# mdv_commutator_v2.net
KiCad netlist of a schematic drawn in Altium Designer
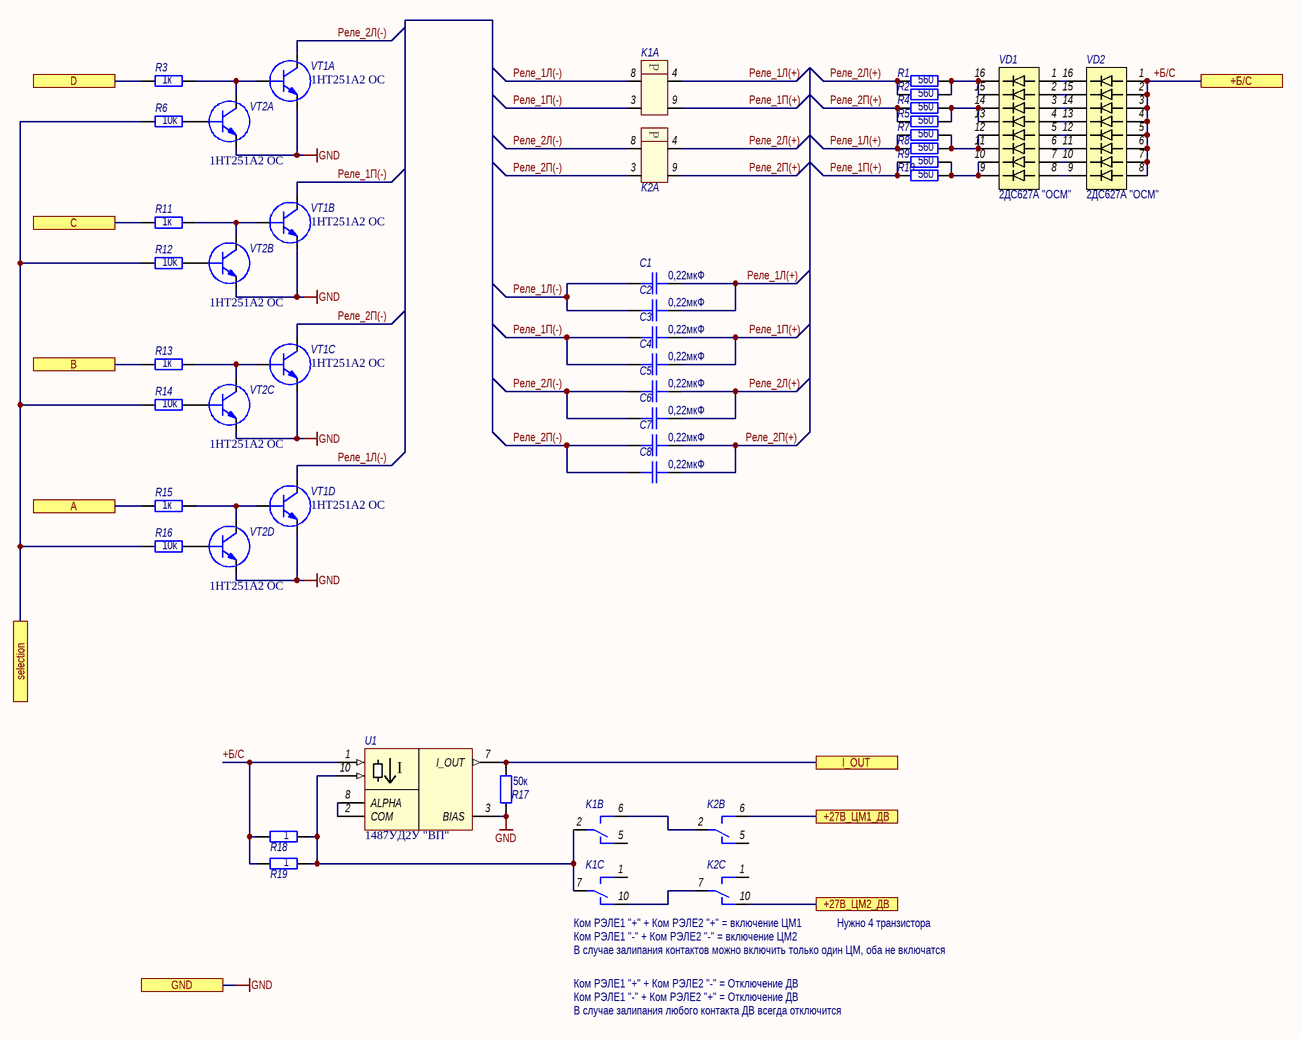
[diagram p0: mdv_commutator_v2.SchDoc]

(export (version "E")
  (design (tool "Eeschema 10.0.6"))
  (components
    (comp (ref "C1")
      (value "0,22мкФ")
      (footprint "SMD_C0402")
      (description "Capacitor")
      (fields (field (name "Comment") "K10-79"))
      (libsource (lib "Passive") (part "Capacitor"))
    )
    (comp (ref "C2")
      (value "0,22мкФ")
      (footprint "SMD_C0402")
      (description "Capacitor")
      (fields (field (name "Comment") "K10-79"))
      (libsource (lib "Passive") (part "Capacitor"))
    )
    (comp (ref "C3")
      (value "0,22мкФ")
      (footprint "SMD_C0402")
      (description "Capacitor")
      (fields (field (name "Comment") "K10-79"))
      (libsource (lib "Passive") (part "Capacitor"))
    )
    (comp (ref "C4")
      (value "0,22мкФ")
      (footprint "SMD_C0402")
      (description "Capacitor")
      (fields (field (name "Comment") "K10-79"))
      (libsource (lib "Passive") (part "Capacitor"))
    )
    (comp (ref "C5")
      (value "0,22мкФ")
      (footprint "SMD_C0402")
      (description "Capacitor")
      (fields (field (name "Comment") "K10-79"))
      (libsource (lib "Passive") (part "Capacitor"))
    )
    (comp (ref "C6")
      (value "0,22мкФ")
      (footprint "SMD_C0402")
      (description "Capacitor")
      (fields (field (name "Comment") "K10-79"))
      (libsource (lib "Passive") (part "Capacitor"))
    )
    (comp (ref "C7")
      (value "0,22мкФ")
      (footprint "SMD_C0402")
      (description "Capacitor")
      (fields (field (name "Comment") "K10-79"))
      (libsource (lib "Passive") (part "Capacitor"))
    )
    (comp (ref "C8")
      (value "0,22мкФ")
      (footprint "SMD_C0402")
      (description "Capacitor")
      (fields (field (name "Comment") "K10-79"))
      (libsource (lib "Passive") (part "Capacitor"))
    )
    (comp (ref "K1")
      (value "RPS45-1-T-OS")
      (footprint "RPS-45-1")
      (description "Реле поляризованное")
      (libsource (lib "Commutator") (part "RPS45"))
    )
    (comp (ref "K2")
      (value "RPS45-1-T-OS")
      (footprint "RPS-45-1")
      (description "Реле поляризованное")
      (libsource (lib "Commutator") (part "RPS45"))
    )
    (comp (ref "R1")
      (value "560")
      (footprint "SMD_0805")
      (description "Resistor")
      (fields (field (name "Comment") "OSM R1-12"))
      (libsource (lib "Passive") (part "Resistor"))
    )
    (comp (ref "R2")
      (value "560")
      (footprint "SMD_0805")
      (description "Resistor")
      (fields (field (name "Comment") "OSM R1-12"))
      (libsource (lib "Passive") (part "Resistor"))
    )
    (comp (ref "R3")
      (value "1к")
      (footprint "SMD_0805")
      (description "Resistor")
      (fields (field (name "Comment") "OSM R1-12"))
      (libsource (lib "Passive") (part "Resistor"))
    )
    (comp (ref "R4")
      (value "560")
      (footprint "SMD_0805")
      (description "Resistor")
      (fields (field (name "Comment") "OSM R1-12"))
      (libsource (lib "Passive") (part "Resistor"))
    )
    (comp (ref "R5")
      (value "560")
      (footprint "SMD_0805")
      (description "Resistor")
      (fields (field (name "Comment") "OSM R1-12"))
      (libsource (lib "Passive") (part "Resistor"))
    )
    (comp (ref "R6")
      (value "10k")
      (footprint "SMD_0805")
      (description "Resistor")
      (fields (field (name "Comment") "OSM R1-12"))
      (libsource (lib "Passive") (part "Resistor"))
    )
    (comp (ref "R7")
      (value "560")
      (footprint "SMD_0805")
      (description "Resistor")
      (fields (field (name "Comment") "OSM R1-12"))
      (libsource (lib "Passive") (part "Resistor"))
    )
    (comp (ref "R8")
      (value "560")
      (footprint "SMD_0805")
      (description "Resistor")
      (fields (field (name "Comment") "OSM R1-12"))
      (libsource (lib "Passive") (part "Resistor"))
    )
    (comp (ref "R9")
      (value "560")
      (footprint "SMD_0805")
      (description "Resistor")
      (fields (field (name "Comment") "OSM R1-12"))
      (libsource (lib "Passive") (part "Resistor"))
    )
    (comp (ref "R10")
      (value "560")
      (footprint "SMD_0805")
      (description "Resistor")
      (fields (field (name "Comment") "OSM R1-12"))
      (libsource (lib "Passive") (part "Resistor"))
    )
    (comp (ref "R11")
      (value "1к")
      (footprint "SMD_0805")
      (description "Resistor")
      (fields (field (name "Comment") "OSM R1-12"))
      (libsource (lib "Passive") (part "Resistor"))
    )
    (comp (ref "R12")
      (value "10k")
      (footprint "SMD_0805")
      (description "Resistor")
      (fields (field (name "Comment") "OSM R1-12"))
      (libsource (lib "Passive") (part "Resistor"))
    )
    (comp (ref "R13")
      (value "1к")
      (footprint "SMD_0805")
      (description "Resistor")
      (fields (field (name "Comment") "OSM R1-12"))
      (libsource (lib "Passive") (part "Resistor"))
    )
    (comp (ref "R14")
      (value "10k")
      (footprint "SMD_0805")
      (description "Resistor")
      (fields (field (name "Comment") "OSM R1-12"))
      (libsource (lib "Passive") (part "Resistor"))
    )
    (comp (ref "R15")
      (value "1к")
      (footprint "SMD_0805")
      (description "Resistor")
      (fields (field (name "Comment") "OSM R1-12"))
      (libsource (lib "Passive") (part "Resistor"))
    )
    (comp (ref "R16")
      (value "10k")
      (footprint "SMD_0805")
      (description "Resistor")
      (fields (field (name "Comment") "OSM R1-12"))
      (libsource (lib "Passive") (part "Resistor"))
    )
    (comp (ref "R17")
      (value "50к")
      (footprint "SMD_0805")
      (description "Resistor")
      (fields (field (name "Comment") "OSM R1-12"))
      (libsource (lib "") (part "Resistor_2"))
    )
    (comp (ref "R18")
      (value "1")
      (footprint "SMD_0805")
      (description "Resistor")
      (fields (field (name "Comment") "OSM R1-12"))
      (libsource (lib "") (part "Resistor_1"))
    )
    (comp (ref "R19")
      (value "1")
      (footprint "SMD_0805")
      (description "Resistor")
      (fields (field (name "Comment") "OSM R1-12"))
      (libsource (lib "") (part "Resistor_1"))
    )
    (comp (ref "U1")
      (value "1487UD2U")
      (footprint "FlatPack-10")
      (fields (field (name "НАИМЕНОВАНИЕ") "1487УД2У \"ВП\""))
      (libsource (lib "Power_Monitor") (part "AD8212S"))
    )
    (comp (ref "VD1")
      (value "2DS627A OSM")
      (footprint "401.16-3")
      (description "Диодная матрица")
      (fields (field (name "НАИМЕНОВАНИЕ") "2ДС627А \"ОСМ\""))
      (libsource (lib "Diod") (part "2DS627A"))
    )
    (comp (ref "VD2")
      (value "2DS627A OSM")
      (footprint "401.16-3")
      (description "Диодная матрица")
      (fields (field (name "НАИМЕНОВАНИЕ") "2ДС627А \"ОСМ\""))
      (libsource (lib "Diod") (part "2DS627A"))
    )
    (comp (ref "VT1")
      (value "1NT251A2 OS")
      (footprint "FlatPack-14.PcbLib")
      (description "Транзисторная сборка")
      (fields (field (name "НАИМЕНОВАНИЕ") "1НТ251А2 ОС"))
      (libsource (lib "1NT251A2 OS") (part "1NT251A2 OS"))
    )
    (comp (ref "VT2")
      (value "1NT251A2 OS")
      (footprint "FlatPack-14.PcbLib")
      (description "Транзисторная сборка")
      (fields (field (name "НАИМЕНОВАНИЕ") "1НТ251А2 ОС"))
      (libsource (lib "1NT251A2 OS") (part "1NT251A2 OS"))
    )
  )
  (nets
    (net (code "1") (name "/+27В_ЦМ1_ДВ") (class "Default")
      (node (ref "K2") (pin "6") (pinfunction "6_6") (pintype "passive"))
    )
    (net (code "2") (name "/+27В_ЦМ2_ДВ") (class "Default")
      (node (ref "K2") (pin "10") (pinfunction "10_10") (pintype "passive"))
    )
    (net (code "3") (name "/+Б{slash}С") (class "Default")
      (node (ref "R18") (pin "2") (pinfunction "2_2") (pintype "passive"))
      (node (ref "R19") (pin "2") (pinfunction "2_2") (pintype "passive"))
      (node (ref "U1") (pin "1") (pinfunction "V+_1") (pintype "input"))
      (node (ref "VD2") (pin "1") (pinfunction "1A_1") (pintype "passive"))
      (node (ref "VD2") (pin "2") (pinfunction "1B_2") (pintype "passive"))
      (node (ref "VD2") (pin "3") (pinfunction "1C_3") (pintype "passive"))
      (node (ref "VD2") (pin "4") (pinfunction "1D_4") (pintype "passive"))
      (node (ref "VD2") (pin "5") (pinfunction "1E_5") (pintype "passive"))
      (node (ref "VD2") (pin "6") (pinfunction "1F_6") (pintype "passive"))
      (node (ref "VD2") (pin "7") (pinfunction "1G_7") (pintype "passive"))
      (node (ref "VD2") (pin "8") (pinfunction "1H_8") (pintype "passive"))
    )
    (net (code "4") (name "/A") (class "Default")
      (node (ref "R15") (pin "1") (pinfunction "1_1") (pintype "passive"))
    )
    (net (code "5") (name "/B") (class "Default")
      (node (ref "R13") (pin "1") (pinfunction "1_1") (pintype "passive"))
    )
    (net (code "6") (name "/C") (class "Default")
      (node (ref "R11") (pin "1") (pinfunction "1_1") (pintype "passive"))
    )
    (net (code "7") (name "/D") (class "Default")
      (node (ref "R3") (pin "1") (pinfunction "1_1") (pintype "passive"))
    )
    (net (code "8") (name "/I_OUT") (class "Default")
      (node (ref "R17") (pin "2") (pinfunction "2_2") (pintype "passive"))
      (node (ref "U1") (pin "7") (pinfunction "I_OUT_7") (pintype "output"))
    )
    (net (code "9") (name "/selection") (class "Default")
      (node (ref "R12") (pin "1") (pinfunction "1_1") (pintype "passive"))
      (node (ref "R14") (pin "1") (pinfunction "1_1") (pintype "passive"))
      (node (ref "R16") (pin "1") (pinfunction "1_1") (pintype "passive"))
      (node (ref "R6") (pin "1") (pinfunction "1_1") (pintype "passive"))
    )
    (net (code "10") (name "/Реле_1Л(+)") (class "Default")
      (node (ref "C1") (pin "2") (pinfunction "2_2") (pintype "passive"))
      (node (ref "C2") (pin "2") (pinfunction "2_2") (pintype "passive"))
      (node (ref "K1") (pin "4") (pinfunction "4_4") (pintype "passive"))
      (node (ref "R7") (pin "1") (pinfunction "1_1") (pintype "passive"))
      (node (ref "R8") (pin "1") (pinfunction "1_1") (pintype "passive"))
    )
    (net (code "11") (name "/Реле_1Л(-)") (class "Default")
      (node (ref "C1") (pin "1") (pinfunction "1_1") (pintype "passive"))
      (node (ref "C2") (pin "1") (pinfunction "1_1") (pintype "passive"))
      (node (ref "K1") (pin "8") (pinfunction "8_8") (pintype "passive"))
      (node (ref "VT1") (pin "7") (pinfunction "C_7") (pintype "passive"))
    )
    (net (code "12") (name "/Реле_1П(+)") (class "Default")
      (node (ref "C3") (pin "2") (pinfunction "2_2") (pintype "passive"))
      (node (ref "C4") (pin "2") (pinfunction "2_2") (pintype "passive"))
      (node (ref "K1") (pin "9") (pinfunction "9_9") (pintype "passive"))
      (node (ref "R10") (pin "1") (pinfunction "1_1") (pintype "passive"))
      (node (ref "R9") (pin "1") (pinfunction "1_1") (pintype "passive"))
    )
    (net (code "13") (name "/Реле_1П(-)") (class "Default")
      (node (ref "C3") (pin "1") (pinfunction "1_1") (pintype "passive"))
      (node (ref "C4") (pin "1") (pinfunction "1_1") (pintype "passive"))
      (node (ref "K1") (pin "3") (pinfunction "3_3") (pintype "passive"))
      (node (ref "VT1") (pin "4") (pinfunction "C_4") (pintype "passive"))
    )
    (net (code "14") (name "/Реле_2Л(+)") (class "Default")
      (node (ref "C5") (pin "2") (pinfunction "2_2") (pintype "passive"))
      (node (ref "C6") (pin "2") (pinfunction "2_2") (pintype "passive"))
      (node (ref "K2") (pin "4") (pinfunction "4_4") (pintype "passive"))
      (node (ref "R1") (pin "1") (pinfunction "1_1") (pintype "passive"))
      (node (ref "R2") (pin "1") (pinfunction "1_1") (pintype "passive"))
    )
    (net (code "15") (name "/Реле_2Л(-)") (class "Default")
      (node (ref "C5") (pin "1") (pinfunction "1_1") (pintype "passive"))
      (node (ref "C6") (pin "1") (pinfunction "1_1") (pintype "passive"))
      (node (ref "K2") (pin "8") (pinfunction "8_8") (pintype "passive"))
      (node (ref "VT1") (pin "14") (pinfunction "C_14") (pintype "passive"))
    )
    (net (code "16") (name "/Реле_2П(+)") (class "Default")
      (node (ref "C7") (pin "2") (pinfunction "2_2") (pintype "passive"))
      (node (ref "C8") (pin "2") (pinfunction "2_2") (pintype "passive"))
      (node (ref "K2") (pin "9") (pinfunction "9_9") (pintype "passive"))
      (node (ref "R4") (pin "1") (pinfunction "1_1") (pintype "passive"))
      (node (ref "R5") (pin "1") (pinfunction "1_1") (pintype "passive"))
    )
    (net (code "17") (name "/Реле_2П(-)") (class "Default")
      (node (ref "C7") (pin "1") (pinfunction "1_1") (pintype "passive"))
      (node (ref "C8") (pin "1") (pinfunction "1_1") (pintype "passive"))
      (node (ref "K2") (pin "3") (pinfunction "3_3") (pintype "passive"))
      (node (ref "VT1") (pin "11") (pinfunction "C_11") (pintype "passive"))
    )
    (net (code "18") (name "GND") (class "Default")
      (node (ref "R17") (pin "1") (pinfunction "1_1") (pintype "passive"))
      (node (ref "U1") (pin "3") (pinfunction "BIAS_3") (pintype "open_collector"))
      (node (ref "VT1") (pin "10") (pinfunction "E_10") (pintype "passive"))
      (node (ref "VT1") (pin "13") (pinfunction "E_13") (pintype "passive"))
      (node (ref "VT1") (pin "3") (pinfunction "E_3") (pintype "passive"))
      (node (ref "VT1") (pin "6") (pinfunction "E_6") (pintype "passive"))
      (node (ref "VT2") (pin "10") (pinfunction "E_10") (pintype "passive"))
      (node (ref "VT2") (pin "13") (pinfunction "E_13") (pintype "passive"))
      (node (ref "VT2") (pin "3") (pinfunction "E_3") (pintype "passive"))
      (node (ref "VT2") (pin "6") (pinfunction "E_6") (pintype "passive"))
    )
    (net (code "19") (name "Net-(K1-Pad6)") (class "Default")
      (node (ref "K1") (pin "6") (pinfunction "6_6") (pintype "passive"))
      (node (ref "K2") (pin "2") (pinfunction "2_2") (pintype "passive"))
    )
    (net (code "20") (name "Net-(K1-Pad10)") (class "Default")
      (node (ref "K1") (pin "10") (pinfunction "10_10") (pintype "passive"))
      (node (ref "K2") (pin "7") (pinfunction "7_7") (pintype "passive"))
    )
    (net (code "21") (name "Net-(R10-Pad2)") (class "Default")
      (node (ref "R10") (pin "2") (pinfunction "2_2") (pintype "passive"))
      (node (ref "R9") (pin "2") (pinfunction "2_2") (pintype "passive"))
      (node (ref "VD1") (pin "10") (pinfunction "2G_10") (pintype "passive"))
      (node (ref "VD1") (pin "9") (pinfunction "2G_9") (pintype "passive"))
    )
    (net (code "22") (name "Net-(U1-ALPHA)") (class "Default")
      (node (ref "U1") (pin "2") (pinfunction "COM_2") (pintype "open_collector"))
      (node (ref "U1") (pin "8") (pinfunction "ALPHA_8") (pintype "open_collector"))
    )
    (net (code "23") (name "Net-(U1-V_SENSE)") (class "Default")
      (node (ref "K1") (pin "2") (pinfunction "2_2") (pintype "passive"))
      (node (ref "K1") (pin "7") (pinfunction "7_7") (pintype "passive"))
      (node (ref "R18") (pin "1") (pinfunction "1_1") (pintype "passive"))
      (node (ref "R19") (pin "1") (pinfunction "1_1") (pintype "passive"))
      (node (ref "U1") (pin "10") (pinfunction "V_SENSE_10") (pintype "input"))
    )
    (net (code "24") (name "Net-(VD1-1A)") (class "Default")
      (node (ref "VD1") (pin "1") (pinfunction "1A_1") (pintype "passive"))
      (node (ref "VD2") (pin "16") (pinfunction "2A_16") (pintype "passive"))
    )
    (net (code "25") (name "Net-(VD1-1B)") (class "Default")
      (node (ref "VD1") (pin "2") (pinfunction "1B_2") (pintype "passive"))
      (node (ref "VD2") (pin "15") (pinfunction "2B_15") (pintype "passive"))
    )
    (net (code "26") (name "Net-(VD1-1C)") (class "Default")
      (node (ref "VD1") (pin "3") (pinfunction "1C_3") (pintype "passive"))
      (node (ref "VD2") (pin "14") (pinfunction "2C_14") (pintype "passive"))
    )
    (net (code "27") (name "Net-(VD1-1D)") (class "Default")
      (node (ref "VD1") (pin "4") (pinfunction "1D_4") (pintype "passive"))
      (node (ref "VD2") (pin "13") (pinfunction "2D_13") (pintype "passive"))
    )
    (net (code "28") (name "Net-(VD1-1E)") (class "Default")
      (node (ref "VD1") (pin "5") (pinfunction "1E_5") (pintype "passive"))
      (node (ref "VD2") (pin "12") (pinfunction "2E_12") (pintype "passive"))
    )
    (net (code "29") (name "Net-(VD1-1F)") (class "Default")
      (node (ref "VD1") (pin "6") (pinfunction "1F_6") (pintype "passive"))
      (node (ref "VD2") (pin "11") (pinfunction "2F_11") (pintype "passive"))
    )
    (net (code "30") (name "Net-(VD1-1G)") (class "Default")
      (node (ref "VD1") (pin "7") (pinfunction "1G_7") (pintype "passive"))
      (node (ref "VD2") (pin "10") (pinfunction "2G_10") (pintype "passive"))
    )
    (net (code "31") (name "Net-(VD1-1H)") (class "Default")
      (node (ref "VD1") (pin "8") (pinfunction "1H_8") (pintype "passive"))
      (node (ref "VD2") (pin "9") (pinfunction "2G_9") (pintype "passive"))
    )
    (net (code "32") (name "Net-(VD1-2A)") (class "Default")
      (node (ref "R1") (pin "2") (pinfunction "2_2") (pintype "passive"))
      (node (ref "R2") (pin "2") (pinfunction "2_2") (pintype "passive"))
      (node (ref "VD1") (pin "15") (pinfunction "2B_15") (pintype "passive"))
      (node (ref "VD1") (pin "16") (pinfunction "2A_16") (pintype "passive"))
    )
    (net (code "33") (name "Net-(VD1-2C)") (class "Default")
      (node (ref "R4") (pin "2") (pinfunction "2_2") (pintype "passive"))
      (node (ref "R5") (pin "2") (pinfunction "2_2") (pintype "passive"))
      (node (ref "VD1") (pin "13") (pinfunction "2D_13") (pintype "passive"))
      (node (ref "VD1") (pin "14") (pinfunction "2C_14") (pintype "passive"))
    )
    (net (code "34") (name "Net-(VD1-2E)") (class "Default")
      (node (ref "R7") (pin "2") (pinfunction "2_2") (pintype "passive"))
      (node (ref "R8") (pin "2") (pinfunction "2_2") (pintype "passive"))
      (node (ref "VD1") (pin "11") (pinfunction "2F_11") (pintype "passive"))
      (node (ref "VD1") (pin "12") (pinfunction "2E_12") (pintype "passive"))
    )
    (net (code "35") (name "Net-(VT1A-B)") (class "Default")
      (node (ref "R3") (pin "2") (pinfunction "2_2") (pintype "passive"))
      (node (ref "VT1") (pin "2") (pinfunction "B_2") (pintype "passive"))
      (node (ref "VT2") (pin "14") (pinfunction "C_14") (pintype "passive"))
    )
    (net (code "36") (name "Net-(VT1B-B)") (class "Default")
      (node (ref "R11") (pin "2") (pinfunction "2_2") (pintype "passive"))
      (node (ref "VT1") (pin "12") (pinfunction "B_12") (pintype "passive"))
      (node (ref "VT2") (pin "4") (pinfunction "C_4") (pintype "passive"))
    )
    (net (code "37") (name "Net-(VT1C-B)") (class "Default")
      (node (ref "R13") (pin "2") (pinfunction "2_2") (pintype "passive"))
      (node (ref "VT1") (pin "5") (pinfunction "B_5") (pintype "passive"))
      (node (ref "VT2") (pin "11") (pinfunction "C_11") (pintype "passive"))
    )
    (net (code "38") (name "Net-(VT1D-B)") (class "Default")
      (node (ref "R15") (pin "2") (pinfunction "2_2") (pintype "passive"))
      (node (ref "VT1") (pin "9") (pinfunction "B_9") (pintype "passive"))
      (node (ref "VT2") (pin "7") (pinfunction "C_7") (pintype "passive"))
    )
    (net (code "39") (name "Net-(VT2A-B)") (class "Default")
      (node (ref "R6") (pin "2") (pinfunction "2_2") (pintype "passive"))
      (node (ref "VT2") (pin "2") (pinfunction "B_2") (pintype "passive"))
    )
    (net (code "40") (name "Net-(VT2B-B)") (class "Default")
      (node (ref "R12") (pin "2") (pinfunction "2_2") (pintype "passive"))
      (node (ref "VT2") (pin "12") (pinfunction "B_12") (pintype "passive"))
    )
    (net (code "41") (name "Net-(VT2C-B)") (class "Default")
      (node (ref "R14") (pin "2") (pinfunction "2_2") (pintype "passive"))
      (node (ref "VT2") (pin "5") (pinfunction "B_5") (pintype "passive"))
    )
    (net (code "42") (name "Net-(VT2D-B)") (class "Default")
      (node (ref "R16") (pin "2") (pinfunction "2_2") (pintype "passive"))
      (node (ref "VT2") (pin "9") (pinfunction "B_9") (pintype "passive"))
    )
    (net (code "43") (name "unconnected-(K1-Pad1)") (class "Default")
      (node (ref "K1") (pin "1") (pinfunction "1_1") (pintype "passive"))
    )
    (net (code "44") (name "unconnected-(K1-Pad5)") (class "Default")
      (node (ref "K1") (pin "5") (pinfunction "5_5") (pintype "passive"))
    )
    (net (code "45") (name "unconnected-(K2-Pad1)") (class "Default")
      (node (ref "K2") (pin "1") (pinfunction "1_1") (pintype "passive"))
    )
    (net (code "46") (name "unconnected-(K2-Pad5)") (class "Default")
      (node (ref "K2") (pin "5") (pinfunction "5_5") (pintype "passive"))
    )
  )
)
